# Power_logger.net
KiCad netlist of a schematic drawn in EasyEDA
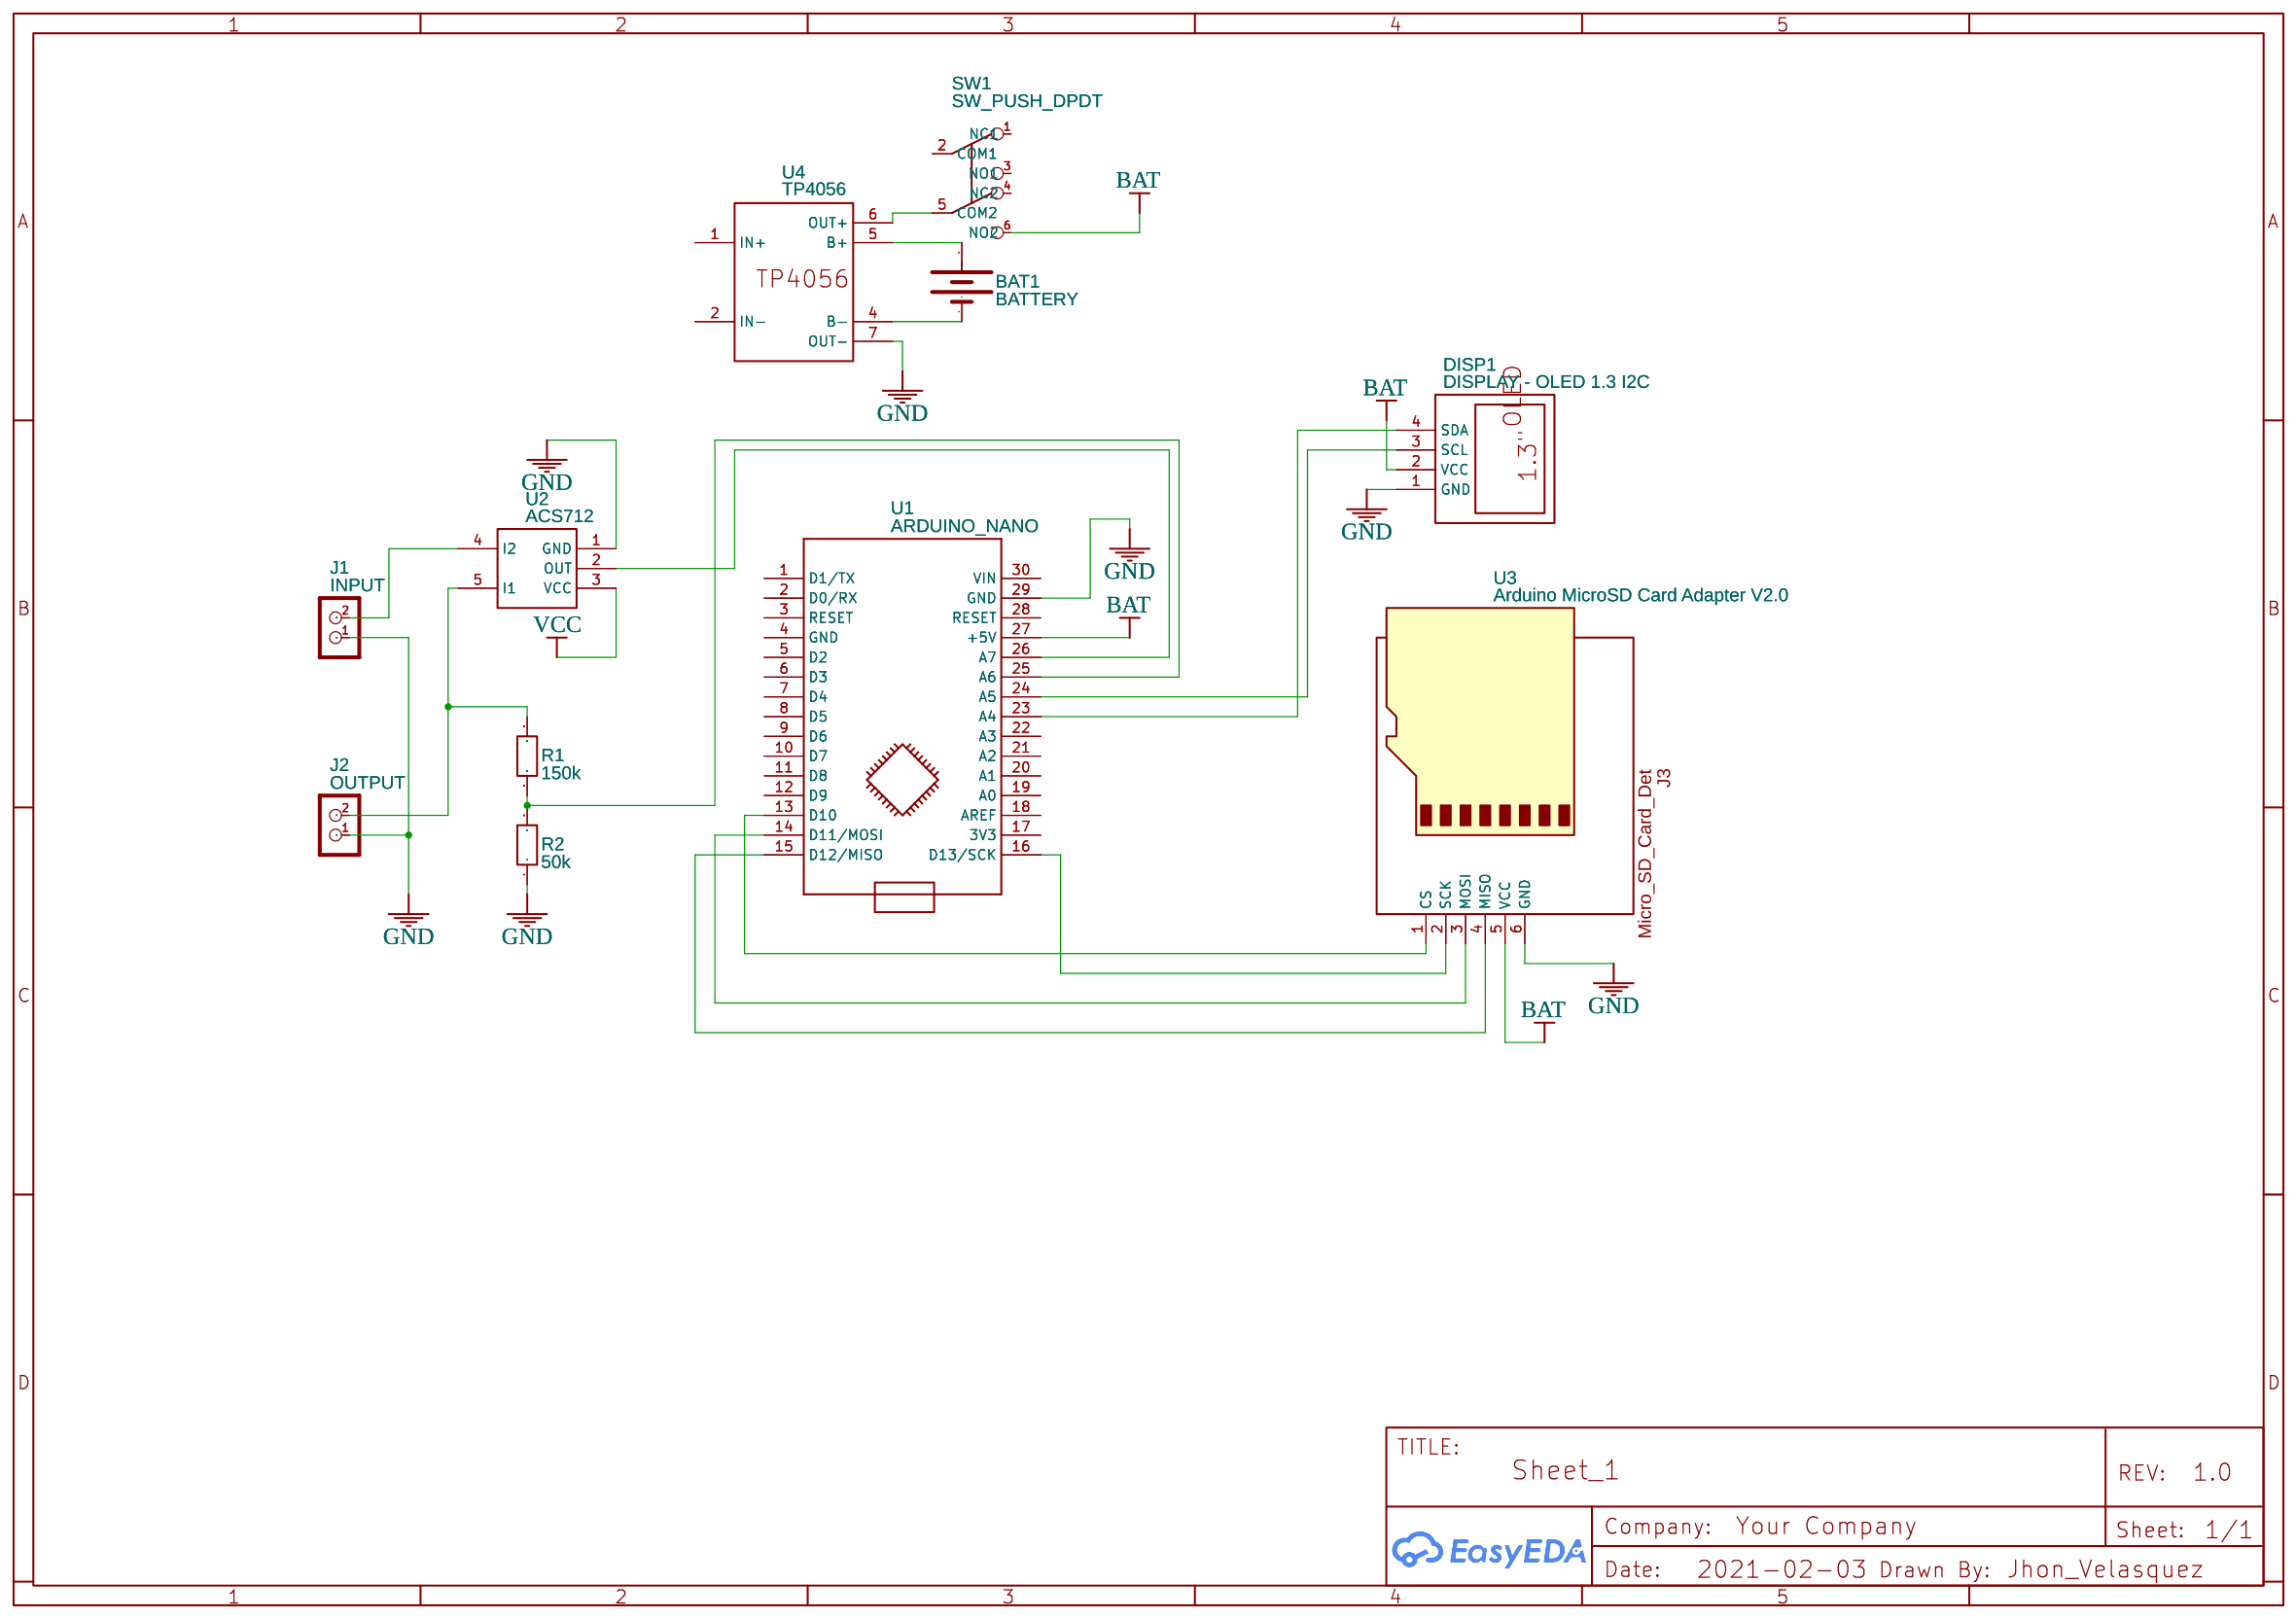
[diagram p0: schematic sheet]

(export (version "E")
  (design (tool "Eeschema 10.0.6"))
  (components
    (comp (ref "BAT1") (value "BATTERY") (libsource (lib "") (part "BATTERY")))
    (comp (ref "DISP1") (value "DISPLAY - OLED 1.3 I2C") (libsource (lib "") (part "DISPLAY - OLED 1.3 I2C")))
    (comp (ref "J1") (value "INPUT") (libsource (lib "") (part "CON_TERMINAL_BLOCK_02")))
    (comp (ref "J2") (value "OUTPUT") (libsource (lib "") (part "CON_TERMINAL_BLOCK_02")))
    (comp (ref "R1") (value "150k") (libsource (lib "") (part "Res_AXIAL-1.0(3W)_EU")))
    (comp (ref "R2") (value "50k") (libsource (lib "") (part "Res_AXIAL-1.0(3W)_EU")))
    (comp (ref "SW1") (value "SW_PUSH_DPDT") (libsource (lib "") (part "SW_PUSH_DPDT")))
    (comp (ref "U1") (value "ARDUINO_NANO") (libsource (lib "") (part "ARDUINO_NANO")))
    (comp (ref "U2") (value "ACS712") (libsource (lib "") (part "ACS712")))
    (comp (ref "U3")
      (value "Arduino MicroSD Card Adapter V2.0")
      (libsource (lib "") (part "Arduino MicroSD Card Adapter V2.0"))
    )
    (comp (ref "U4")
      (value "TP4056")
      (fields (field (name "BOM_Manufacturer Part") "TP4056-protect"))
      (libsource (lib "") (part "TP4056"))
    )
  )
  (nets
    (net (code "1") (name "BAT") (class "Default")
      (node (ref "DISP1") (pin "2") (pinfunction "VCC_2") (pintype "bidirectional"))
      (node (ref "SW1") (pin "6") (pinfunction "NO2_6") (pintype "unspecified"))
      (node (ref "U1") (pin "27") (pinfunction "+5V_27") (pintype "unspecified"))
      (node (ref "U3") (pin "5") (pinfunction "VCC_5") (pintype "unspecified"))
    )
    (net (code "2") (name "GND") (class "Default")
      (node (ref "DISP1") (pin "1") (pinfunction "GND_1") (pintype "bidirectional"))
      (node (ref "J1") (pin "1") (pinfunction "1_1") (pintype "unspecified"))
      (node (ref "J2") (pin "1") (pinfunction "1_1") (pintype "unspecified"))
      (node (ref "R2") (pin "1") (pinfunction "1_1") (pintype "unspecified"))
      (node (ref "U1") (pin "29") (pinfunction "GND_29") (pintype "unspecified"))
      (node (ref "U2") (pin "1") (pinfunction "GND_1") (pintype "unspecified"))
      (node (ref "U3") (pin "6") (pinfunction "GND_6") (pintype "unspecified"))
      (node (ref "U4") (pin "7") (pinfunction "OUT-_7") (pintype "unspecified"))
    )
    (net (code "3") (name "Net-(DISP1-SCL)") (class "Default")
      (node (ref "DISP1") (pin "3") (pinfunction "SCL_3") (pintype "passive"))
      (node (ref "U1") (pin "24") (pinfunction "A5_24") (pintype "unspecified"))
    )
    (net (code "4") (name "Net-(DISP1-SDA)") (class "Default")
      (node (ref "DISP1") (pin "4") (pinfunction "SDA_4") (pintype "passive"))
      (node (ref "U1") (pin "23") (pinfunction "A4_23") (pintype "unspecified"))
    )
    (net (code "5") (name "Net-(SW1-COM2)") (class "Default")
      (node (ref "SW1") (pin "5") (pinfunction "COM2_5") (pintype "unspecified"))
      (node (ref "U4") (pin "6") (pinfunction "OUT+_6") (pintype "unspecified"))
    )
    (net (code "6") (name "Net-(U1-A6)") (class "Default")
      (node (ref "R1") (pin "1") (pinfunction "1_1") (pintype "unspecified"))
      (node (ref "R2") (pin "2") (pinfunction "2_2") (pintype "unspecified"))
      (node (ref "U1") (pin "25") (pinfunction "A6_25") (pintype "unspecified"))
    )
    (net (code "7") (name "Net-(U1-A7)") (class "Default")
      (node (ref "U1") (pin "26") (pinfunction "A7_26") (pintype "unspecified"))
      (node (ref "U2") (pin "2") (pinfunction "OUT_2") (pintype "unspecified"))
    )
    (net (code "8") (name "Net-(U1-D10)") (class "Default")
      (node (ref "U1") (pin "13") (pinfunction "D10_13") (pintype "unspecified"))
      (node (ref "U3") (pin "1") (pinfunction "CS_1") (pintype "unspecified"))
    )
    (net (code "9") (name "Net-(U1-D11{slash}MOSI)") (class "Default")
      (node (ref "U1") (pin "14") (pinfunction "D11/MOSI_14") (pintype "unspecified"))
      (node (ref "U3") (pin "3") (pinfunction "MOSI_3") (pintype "unspecified"))
    )
    (net (code "10") (name "Net-(U1-D12{slash}MISO)") (class "Default")
      (node (ref "U1") (pin "15") (pinfunction "D12/MISO_15") (pintype "unspecified"))
      (node (ref "U3") (pin "4") (pinfunction "MISO_4") (pintype "unspecified"))
    )
    (net (code "11") (name "Net-(U1-D13{slash}SCK)") (class "Default")
      (node (ref "U1") (pin "16") (pinfunction "D13/SCK_16") (pintype "unspecified"))
      (node (ref "U3") (pin "2") (pinfunction "SCK_2") (pintype "unspecified"))
    )
    (net (code "12") (name "Net-(U2-I1)") (class "Default")
      (node (ref "J2") (pin "2") (pinfunction "2_2") (pintype "unspecified"))
      (node (ref "R1") (pin "2") (pinfunction "2_2") (pintype "unspecified"))
      (node (ref "U2") (pin "5") (pinfunction "I1_5") (pintype "unspecified"))
    )
    (net (code "13") (name "Net-(U2-I2)") (class "Default")
      (node (ref "J1") (pin "2") (pinfunction "2_2") (pintype "unspecified"))
      (node (ref "U2") (pin "4") (pinfunction "I2_4") (pintype "unspecified"))
    )
    (net (code "14") (name "Net-(U4-B+)") (class "Default")
      (node (ref "BAT1") (pin "+") (pinfunction "+_+") (pintype "passive"))
      (node (ref "U4") (pin "5") (pinfunction "B+_5") (pintype "unspecified"))
    )
    (net (code "15") (name "Net-(U4-B-)") (class "Default")
      (node (ref "BAT1") (pin "-") (pinfunction "-_-") (pintype "passive"))
      (node (ref "U4") (pin "4") (pinfunction "B-_4") (pintype "unspecified"))
    )
    (net (code "16") (name "VCC") (class "Default")
      (node (ref "U2") (pin "3") (pinfunction "VCC_3") (pintype "unspecified"))
    )
    (net (code "17") (name "unconnected-(SW1-COM1-Pad2)") (class "Default")
      (node (ref "SW1") (pin "2") (pinfunction "COM1_2") (pintype "unspecified"))
    )
    (net (code "18") (name "unconnected-(SW1-NC1-Pad1)") (class "Default")
      (node (ref "SW1") (pin "1") (pinfunction "NC1_1") (pintype "unspecified"))
    )
    (net (code "19") (name "unconnected-(SW1-NC2-Pad4)") (class "Default")
      (node (ref "SW1") (pin "4") (pinfunction "NC2_4") (pintype "unspecified"))
    )
    (net (code "20") (name "unconnected-(SW1-NO1-Pad3)") (class "Default")
      (node (ref "SW1") (pin "3") (pinfunction "NO1_3") (pintype "unspecified"))
    )
    (net (code "21") (name "unconnected-(U1-3V3-Pad17)") (class "Default")
      (node (ref "U1") (pin "17") (pinfunction "3V3_17") (pintype "unspecified"))
    )
    (net (code "22") (name "unconnected-(U1-A0-Pad19)") (class "Default")
      (node (ref "U1") (pin "19") (pinfunction "A0_19") (pintype "unspecified"))
    )
    (net (code "23") (name "unconnected-(U1-A1-Pad20)") (class "Default")
      (node (ref "U1") (pin "20") (pinfunction "A1_20") (pintype "unspecified"))
    )
    (net (code "24") (name "unconnected-(U1-A2-Pad21)") (class "Default")
      (node (ref "U1") (pin "21") (pinfunction "A2_21") (pintype "unspecified"))
    )
    (net (code "25") (name "unconnected-(U1-A3-Pad22)") (class "Default")
      (node (ref "U1") (pin "22") (pinfunction "A3_22") (pintype "unspecified"))
    )
    (net (code "26") (name "unconnected-(U1-AREF-Pad18)") (class "Default")
      (node (ref "U1") (pin "18") (pinfunction "AREF_18") (pintype "unspecified"))
    )
    (net (code "27") (name "unconnected-(U1-D0{slash}RX-Pad2)") (class "Default")
      (node (ref "U1") (pin "2") (pinfunction "D0/RX_2") (pintype "unspecified"))
    )
    (net (code "28") (name "unconnected-(U1-D1{slash}TX-Pad1)") (class "Default")
      (node (ref "U1") (pin "1") (pinfunction "D1/TX_1") (pintype "unspecified"))
    )
    (net (code "29") (name "unconnected-(U1-D2-Pad5)") (class "Default")
      (node (ref "U1") (pin "5") (pinfunction "D2_5") (pintype "unspecified"))
    )
    (net (code "30") (name "unconnected-(U1-D3-Pad6)") (class "Default")
      (node (ref "U1") (pin "6") (pinfunction "D3_6") (pintype "unspecified"))
    )
    (net (code "31") (name "unconnected-(U1-D4-Pad7)") (class "Default")
      (node (ref "U1") (pin "7") (pinfunction "D4_7") (pintype "unspecified"))
    )
    (net (code "32") (name "unconnected-(U1-D5-Pad8)") (class "Default")
      (node (ref "U1") (pin "8") (pinfunction "D5_8") (pintype "unspecified"))
    )
    (net (code "33") (name "unconnected-(U1-D6-Pad9)") (class "Default")
      (node (ref "U1") (pin "9") (pinfunction "D6_9") (pintype "unspecified"))
    )
    (net (code "34") (name "unconnected-(U1-D7-Pad10)") (class "Default")
      (node (ref "U1") (pin "10") (pinfunction "D7_10") (pintype "unspecified"))
    )
    (net (code "35") (name "unconnected-(U1-D8-Pad11)") (class "Default")
      (node (ref "U1") (pin "11") (pinfunction "D8_11") (pintype "unspecified"))
    )
    (net (code "36") (name "unconnected-(U1-D9-Pad12)") (class "Default")
      (node (ref "U1") (pin "12") (pinfunction "D9_12") (pintype "unspecified"))
    )
    (net (code "37") (name "unconnected-(U1-GND-Pad4)") (class "Default")
      (node (ref "U1") (pin "4") (pinfunction "GND_4") (pintype "unspecified"))
    )
    (net (code "38") (name "unconnected-(U1-RESET-Pad3)") (class "Default")
      (node (ref "U1") (pin "3") (pinfunction "RESET_3") (pintype "unspecified"))
    )
    (net (code "39") (name "unconnected-(U1-RESET-Pad28)") (class "Default")
      (node (ref "U1") (pin "28") (pinfunction "RESET_28") (pintype "unspecified"))
    )
    (net (code "40") (name "unconnected-(U1-VIN-Pad30)") (class "Default")
      (node (ref "U1") (pin "30") (pinfunction "VIN_30") (pintype "unspecified"))
    )
    (net (code "41") (name "unconnected-(U4-IN+-Pad1)") (class "Default")
      (node (ref "U4") (pin "1") (pinfunction "IN+_1") (pintype "unspecified"))
    )
    (net (code "42") (name "unconnected-(U4-IN--Pad2)") (class "Default")
      (node (ref "U4") (pin "2") (pinfunction "IN-_2") (pintype "unspecified"))
    )
  )
)
